# Qwiic_Proximity_Sensor_-_VCNL4040.net
KiCad netlist of a schematic drawn in EAGLE
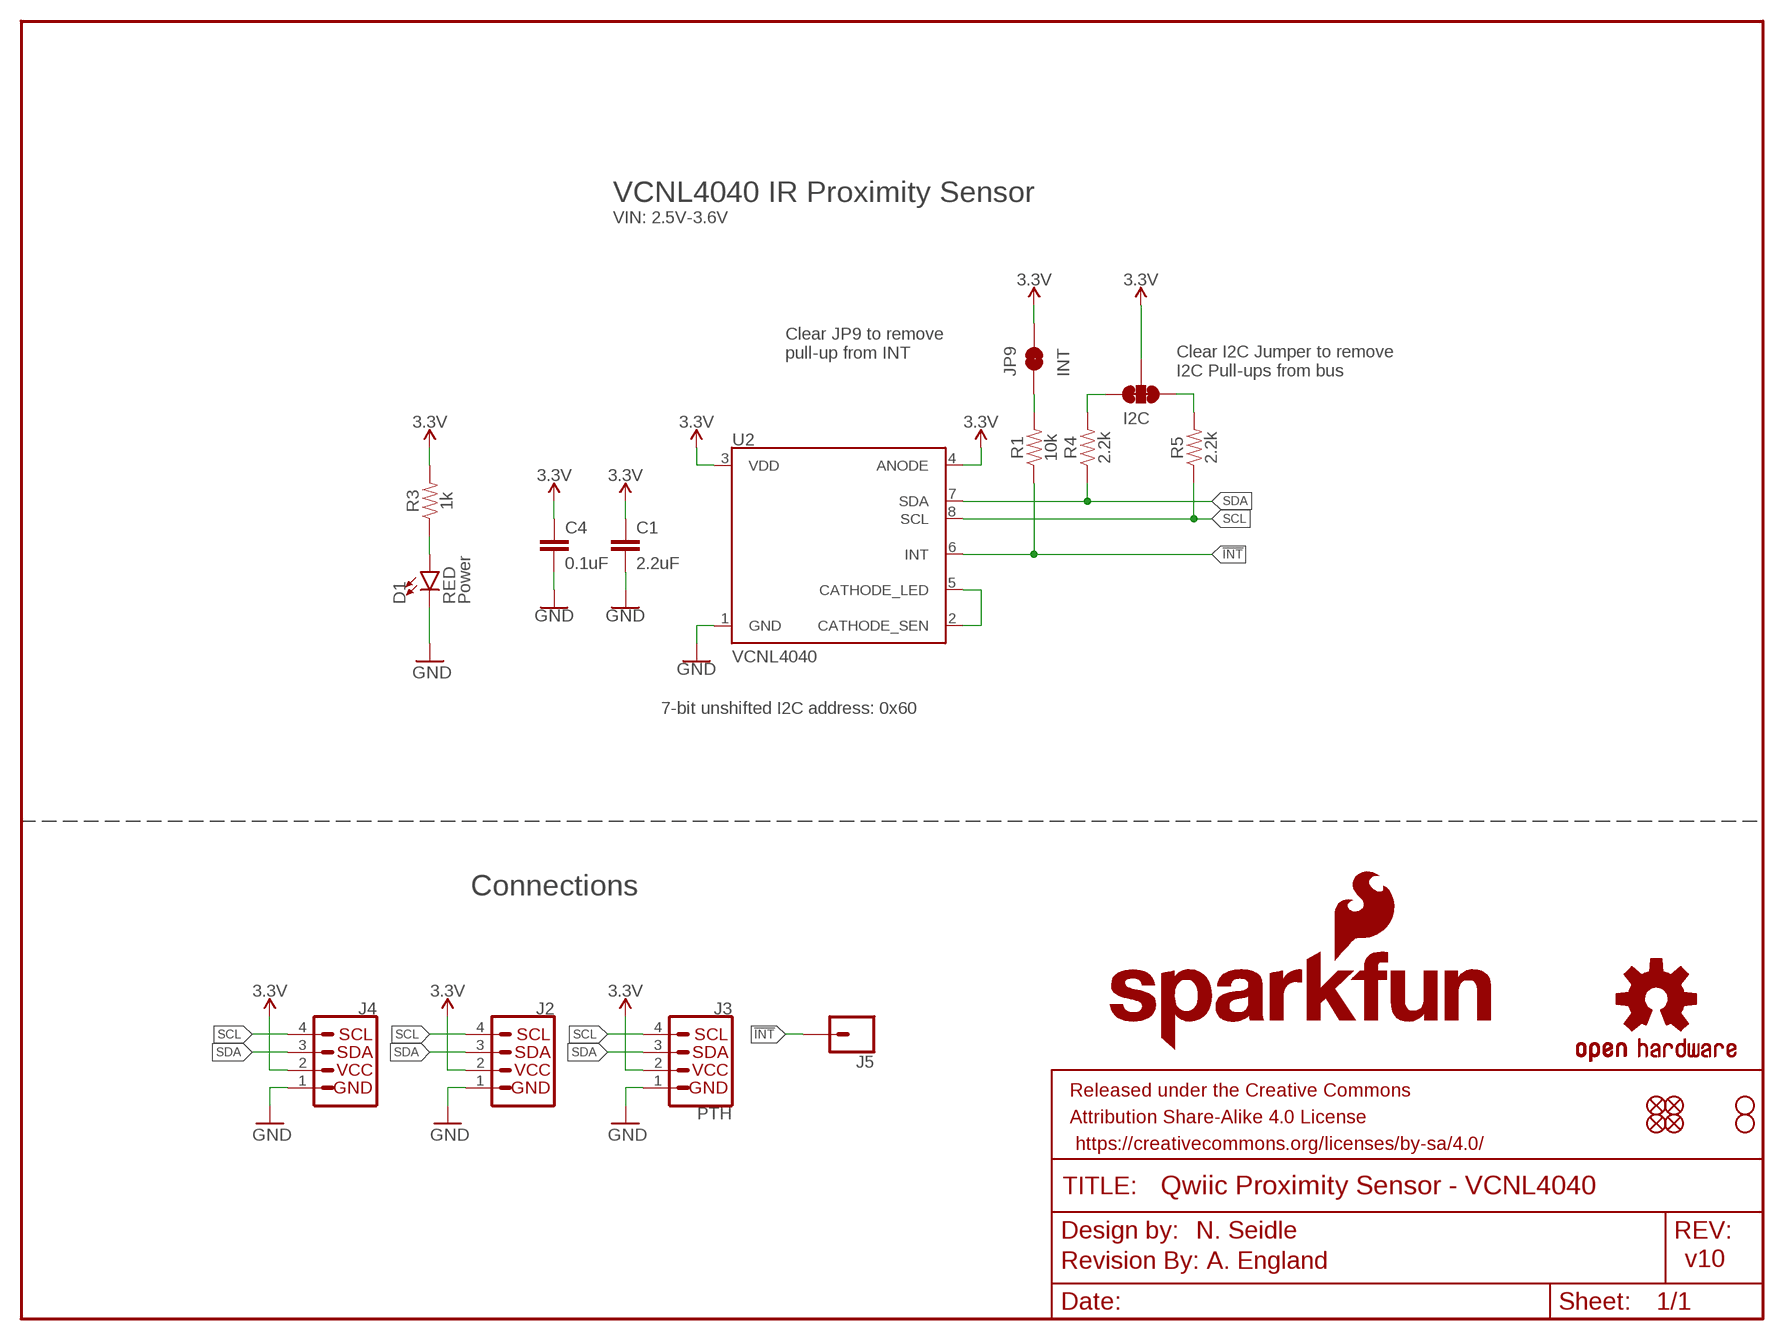
[diagram p0: schematic, sheet 1]

(export (version "E")
  (design (tool "Eeschema 10.0.6"))
  (components
    (comp (ref "C1")
      (value "2.2uF")
      (footprint "eagle-import:0603")
      (libsource (lib "eagle-import") (part "2.2UF-0603-10V-20%"))
    )
    (comp (ref "C4")
      (value "0.1uF")
      (footprint "eagle-import:0603")
      (libsource (lib "eagle-import") (part "0.1UF-0603-25V-(+80/-20%)"))
    )
    (comp (ref "D1")
      (value "RED")
      (footprint "eagle-import:LED-0603")
      (libsource (lib "eagle-import") (part "LED-RED0603"))
    )
    (comp (ref "FRAME1")
      (value "FRAME-LETTER")
      (footprint "eagle-import:CREATIVE_COMMONS")
      (libsource (lib "eagle-import") (part "FRAME-LETTER"))
    )
    (comp (ref "I2C")
      (value "JUMPER-SMT_3_2-NC_TRACE_SILK")
      (footprint "eagle-import:SMT-JUMPER_3_2-NC_TRACE_SILK")
      (libsource (lib "eagle-import") (part "JUMPER-SMT_3_2-NC_TRACE_SILK"))
    )
    (comp (ref "J2")
      (value "QWIIC_CONNECTORJS-1MM")
      (footprint "eagle-import:1X04_1MM_RA")
      (libsource (lib "eagle-import") (part "QWIIC_CONNECTORJS-1MM"))
    )
    (comp (ref "J3")
      (value "PTH")
      (footprint "eagle-import:1X04_NO_SILK")
      (libsource (lib "eagle-import") (part "I2C_STANDARD_NO_SILK"))
    )
    (comp (ref "J4")
      (value "QWIIC_CONNECTORJS-1MM")
      (footprint "eagle-import:1X04_1MM_RA")
      (libsource (lib "eagle-import") (part "QWIIC_CONNECTORJS-1MM"))
    )
    (comp (ref "J5")
      (value "CONN_01PTH_NO_SILK_YES_STOP")
      (footprint "eagle-import:1X01_NO_SILK")
      (libsource (lib "eagle-import") (part "CONN_01PTH_NO_SILK_YES_STOP"))
    )
    (comp (ref "JP1")
      (value "FIDUCIALUFIDUCIAL")
      (footprint "eagle-import:MICRO-FIDUCIAL")
      (libsource (lib "eagle-import") (part "FIDUCIALUFIDUCIAL"))
    )
    (comp (ref "JP2")
      (value "FIDUCIALUFIDUCIAL")
      (footprint "eagle-import:MICRO-FIDUCIAL")
      (libsource (lib "eagle-import") (part "FIDUCIALUFIDUCIAL"))
    )
    (comp (ref "JP3")
      (value "STAND-OFF")
      (footprint "eagle-import:STAND-OFF")
      (libsource (lib "eagle-import") (part "STAND-OFF"))
    )
    (comp (ref "JP4")
      (value "STAND-OFF")
      (footprint "eagle-import:STAND-OFF")
      (libsource (lib "eagle-import") (part "STAND-OFF"))
    )
    (comp (ref "JP5")
      (value "FIDUCIALUFIDUCIAL")
      (footprint "eagle-import:MICRO-FIDUCIAL")
      (libsource (lib "eagle-import") (part "FIDUCIALUFIDUCIAL"))
    )
    (comp (ref "JP6")
      (value "FIDUCIALUFIDUCIAL")
      (footprint "eagle-import:MICRO-FIDUCIAL")
      (libsource (lib "eagle-import") (part "FIDUCIALUFIDUCIAL"))
    )
    (comp (ref "JP9")
      (value "INT")
      (footprint "eagle-import:PAD-JUMPER-2-NC_BY_TRACE_YES_SILK")
      (libsource (lib "eagle-import") (part "JUMPER-PAD-2-NC_BY_TRACE"))
    )
    (comp (ref "LOGO1")
      (value "OSHW-LOGOMINI")
      (footprint "eagle-import:OSHW-LOGO-MINI")
      (libsource (lib "eagle-import") (part "OSHW-LOGOMINI"))
    )
    (comp (ref "LOGO2")
      (value "REVISION")
      (footprint "eagle-import:REVISION")
      (libsource (lib "eagle-import") (part "REVISION"))
    )
    (comp (ref "R1")
      (value "10k")
      (footprint "eagle-import:0603")
      (libsource (lib "eagle-import") (part "10KOHM-0603-1/10W-1%"))
    )
    (comp (ref "R3")
      (value "1k")
      (footprint "eagle-import:0603")
      (libsource (lib "eagle-import") (part "1KOHM-0603-1/10W-1%"))
    )
    (comp (ref "R4")
      (value "2.2k")
      (footprint "eagle-import:0603")
      (libsource (lib "eagle-import") (part "2.2KOHM-0603-1/10W-1%"))
    )
    (comp (ref "R5")
      (value "2.2k")
      (footprint "eagle-import:0603")
      (libsource (lib "eagle-import") (part "2.2KOHM-0603-1/10W-1%"))
    )
    (comp (ref "U$1")
      (value "SFE_LOGO_NAME_FLAME.1_INCH")
      (footprint "eagle-import:SFE_LOGO_NAME_FLAME_.1")
      (libsource (lib "eagle-import") (part "SFE_LOGO_NAME_FLAME.1_INCH"))
    )
    (comp (ref "U$2")
      (value "SFE_LOGO_NAME_FLAME.1_INCH")
      (footprint "eagle-import:SFE_LOGO_NAME_FLAME_.1")
      (libsource (lib "eagle-import") (part "SFE_LOGO_NAME_FLAME.1_INCH"))
    )
    (comp (ref "U2")
      (value "VCNL4040")
      (footprint "eagle-import:SPARKX_VCNL4040")
      (libsource (lib "eagle-import") (part "VCNL4040"))
    )
  )
  (nets
    (net (code "1") (name "/~{INT}") (class "Default")
      (node (ref "J5") (pin "1") (pinfunction "1_1") (pintype "passive"))
      (node (ref "R1") (pin "1") (pinfunction "1_1") (pintype "passive"))
      (node (ref "U2") (pin "6") (pinfunction "INT_6") (pintype "bidirectional"))
    )
    (net (code "2") (name "3.3V") (class "Default")
      (node (ref "C1") (pin "1") (pinfunction "1_1") (pintype "passive"))
      (node (ref "C4") (pin "1") (pinfunction "1_1") (pintype "passive"))
      (node (ref "I2C") (pin "2") (pinfunction "2_2") (pintype "passive"))
      (node (ref "J2") (pin "2") (pinfunction "2_2") (pintype "power_in"))
      (node (ref "J3") (pin "2") (pinfunction "VCC_2") (pintype "power_in"))
      (node (ref "J4") (pin "2") (pinfunction "2_2") (pintype "power_in"))
      (node (ref "JP9") (pin "2") (pinfunction "2_2") (pintype "passive"))
      (node (ref "R3") (pin "2") (pinfunction "2_2") (pintype "passive"))
      (node (ref "U2") (pin "3") (pinfunction "VDD_3") (pintype "bidirectional"))
      (node (ref "U2") (pin "4") (pinfunction "ANODE_4") (pintype "bidirectional"))
    )
    (net (code "3") (name "GND") (class "Default")
      (node (ref "C1") (pin "2") (pinfunction "2_2") (pintype "passive"))
      (node (ref "C4") (pin "2") (pinfunction "2_2") (pintype "passive"))
      (node (ref "D1") (pin "C") (pinfunction "C_C") (pintype "passive"))
      (node (ref "J2") (pin "1") (pinfunction "1_1") (pintype "power_in"))
      (node (ref "J3") (pin "1") (pinfunction "GND_1") (pintype "power_in"))
      (node (ref "J4") (pin "1") (pinfunction "1_1") (pintype "power_in"))
      (node (ref "U2") (pin "1") (pinfunction "GND_1") (pintype "bidirectional"))
    )
    (net (code "4") (name "Net-(D1-PadA)") (class "Default")
      (node (ref "D1") (pin "A") (pinfunction "A_A") (pintype "passive"))
      (node (ref "R3") (pin "1") (pinfunction "1_1") (pintype "passive"))
    )
    (net (code "5") (name "Net-(I2C-Pad1)") (class "Default")
      (node (ref "I2C") (pin "1") (pinfunction "1_1") (pintype "passive"))
      (node (ref "R5") (pin "2") (pinfunction "2_2") (pintype "passive"))
    )
    (net (code "6") (name "Net-(I2C-Pad3)") (class "Default")
      (node (ref "I2C") (pin "3") (pinfunction "3_3") (pintype "passive"))
      (node (ref "R4") (pin "2") (pinfunction "2_2") (pintype "passive"))
    )
    (net (code "7") (name "Net-(JP9-Pad1)") (class "Default")
      (node (ref "JP9") (pin "1") (pinfunction "1_1") (pintype "passive"))
      (node (ref "R1") (pin "2") (pinfunction "2_2") (pintype "passive"))
    )
    (net (code "8") (name "Net-(U2-CATHODE_LED)") (class "Default")
      (node (ref "U2") (pin "2") (pinfunction "CATHODE_SEN_2") (pintype "bidirectional"))
      (node (ref "U2") (pin "5") (pinfunction "CATHODE_LED_5") (pintype "bidirectional"))
    )
    (net (code "9") (name "SCL") (class "Default")
      (node (ref "J2") (pin "4") (pinfunction "4_4") (pintype "passive"))
      (node (ref "J3") (pin "4") (pinfunction "SCL_4") (pintype "passive"))
      (node (ref "J4") (pin "4") (pinfunction "4_4") (pintype "passive"))
      (node (ref "R5") (pin "1") (pinfunction "1_1") (pintype "passive"))
      (node (ref "U2") (pin "8") (pinfunction "SCL_8") (pintype "bidirectional"))
    )
    (net (code "10") (name "SDA") (class "Default")
      (node (ref "J2") (pin "3") (pinfunction "3_3") (pintype "passive"))
      (node (ref "J3") (pin "3") (pinfunction "SDA_3") (pintype "passive"))
      (node (ref "J4") (pin "3") (pinfunction "3_3") (pintype "passive"))
      (node (ref "R4") (pin "1") (pinfunction "1_1") (pintype "passive"))
      (node (ref "U2") (pin "7") (pinfunction "SDA_7") (pintype "bidirectional"))
    )
  )
)
